# touch-24-v2.net
KiCad netlist of a schematic drawn in Altium Designer
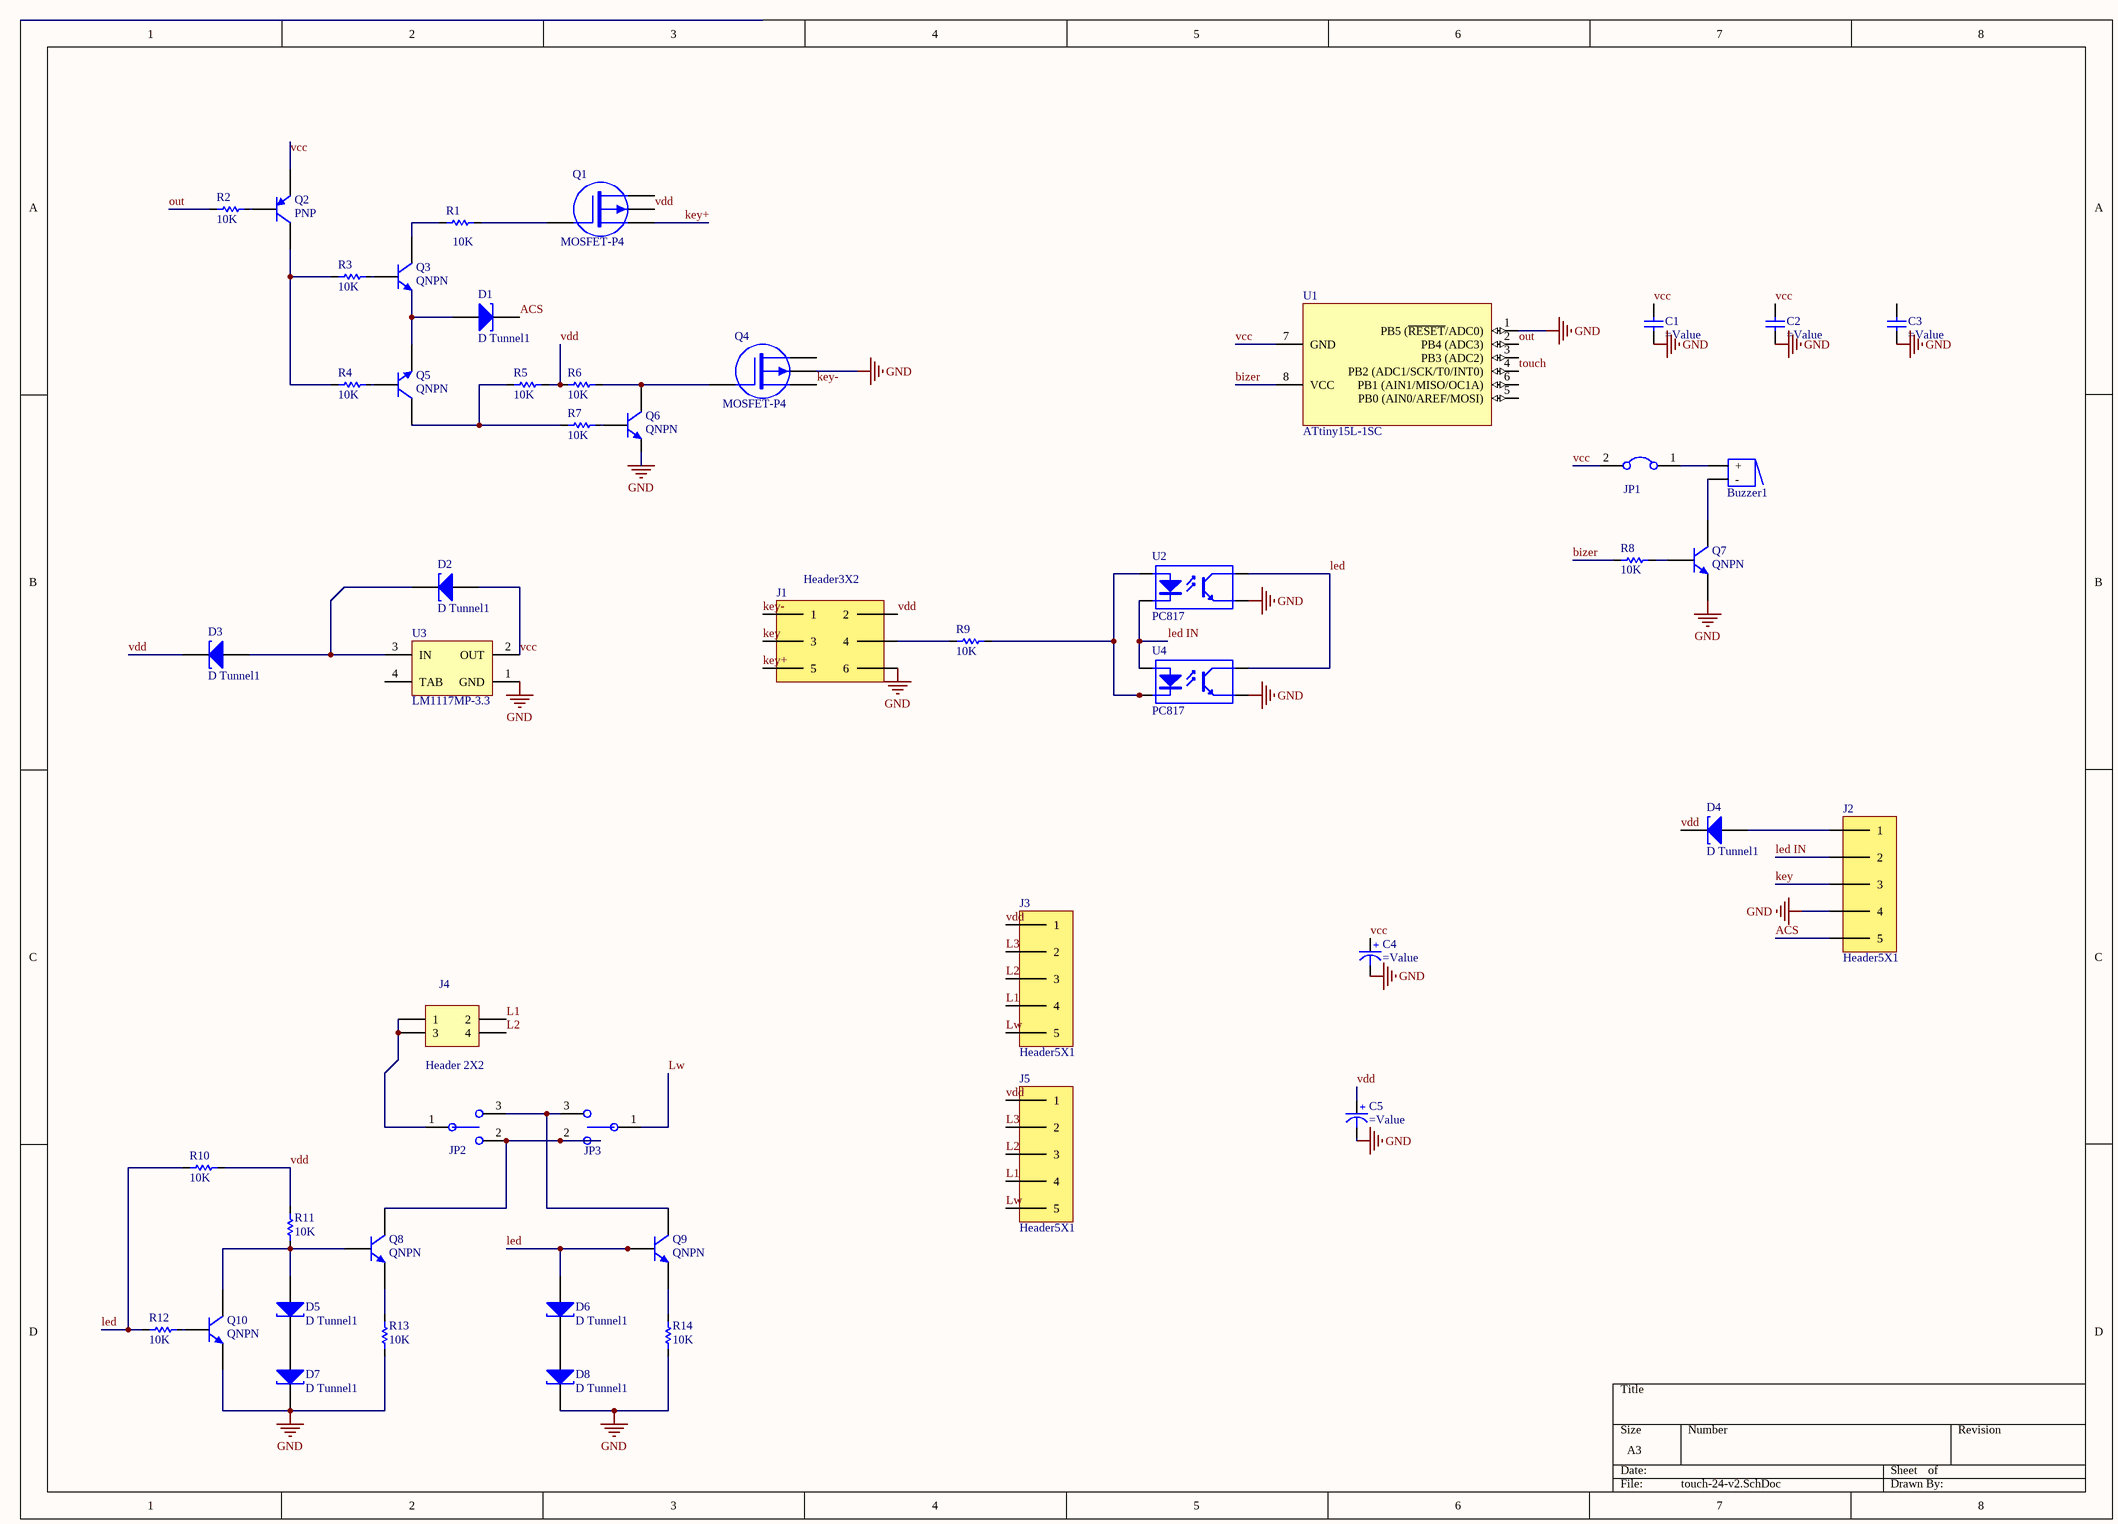
[diagram p0: touch-24-v2.SchDoc]

(export (version "E")
  (design (tool "Eeschema 10.0.6"))
  (components
    (comp (ref "Buzzer1")
      (value "Buzzer")
      (footprint "BUZZER")
      (fields (field (name "DESIGNER") "Seyed Mohsen Ghasemain"))
      (libsource (lib "PicPars.com_usefully_Library") (part "Buzzer"))
    )
    (comp (ref "C1")
      (value "~")
      (footprint "CAP 1206")
      (description "Capacitor")
      (libsource (lib "AltiumLib1") (part "Capacitor"))
    )
    (comp (ref "C2")
      (value "~")
      (footprint "CAP 1206")
      (description "Capacitor")
      (libsource (lib "AltiumLib1") (part "Capacitor"))
    )
    (comp (ref "C3")
      (value "~")
      (footprint "CAP 1206")
      (description "Capacitor")
      (libsource (lib "AltiumLib1") (part "Capacitor"))
    )
    (comp (ref "C4")
      (value "~")
      (footprint "ELEC-CAP-RAD10-20")
      (description "Electrolytic Capacitor")
      (libsource (lib "AltiumLib1") (part "Capacitor Electrolytic"))
    )
    (comp (ref "C5")
      (value "~")
      (footprint "ELEC-CAP-RAD15-30")
      (description "Electrolytic Capacitor")
      (libsource (lib "AltiumLib1") (part "Capacitor Electrolytic"))
    )
    (comp (ref "D1")
      (value "D Tunnel1")
      (footprint "3.2X1.6X1.1")
      (description "Tunnel Diode - RLC Model")
      (fields (field (name "PUBLISHER") "Altium Limited"))
      (libsource (lib "Miscellaneous Devices") (part "D Tunnel1"))
    )
    (comp (ref "D2")
      (value "D Tunnel1")
      (footprint "3.2X1.6X1.1")
      (description "Tunnel Diode - RLC Model")
      (fields (field (name "PUBLISHER") "Altium Limited"))
      (libsource (lib "Miscellaneous Devices") (part "D Tunnel1"))
    )
    (comp (ref "D3")
      (value "D Tunnel1")
      (footprint "3.2X1.6X1.1")
      (description "Tunnel Diode - RLC Model")
      (fields (field (name "PUBLISHER") "Altium Limited"))
      (libsource (lib "Miscellaneous Devices") (part "D Tunnel1"))
    )
    (comp (ref "D4")
      (value "D Tunnel1")
      (footprint "3.2X1.6X1.1")
      (description "Tunnel Diode - RLC Model")
      (fields (field (name "PUBLISHER") "Altium Limited"))
      (libsource (lib "Miscellaneous Devices") (part "D Tunnel1"))
    )
    (comp (ref "D5")
      (value "D Tunnel1")
      (footprint "3.2X1.6X1.1")
      (description "Tunnel Diode - RLC Model")
      (fields (field (name "PUBLISHER") "Altium Limited"))
      (libsource (lib "Miscellaneous Devices") (part "D Tunnel1"))
    )
    (comp (ref "D6")
      (value "D Tunnel1")
      (footprint "3.2X1.6X1.1")
      (description "Tunnel Diode - RLC Model")
      (fields (field (name "PUBLISHER") "Altium Limited"))
      (libsource (lib "Miscellaneous Devices") (part "D Tunnel1"))
    )
    (comp (ref "D7")
      (value "D Tunnel1")
      (footprint "3.2X1.6X1.1")
      (description "Tunnel Diode - RLC Model")
      (fields (field (name "PUBLISHER") "Altium Limited"))
      (libsource (lib "Miscellaneous Devices") (part "D Tunnel1"))
    )
    (comp (ref "D8")
      (value "D Tunnel1")
      (footprint "3.2X1.6X1.1")
      (description "Tunnel Diode - RLC Model")
      (fields (field (name "PUBLISHER") "Altium Limited"))
      (libsource (lib "Miscellaneous Devices") (part "D Tunnel1"))
    )
    (comp (ref "J1")
      (value "Header3X2")
      (footprint "HEADER 3X2")
      (libsource (lib "AltiumLib1") (part "Header3X2"))
    )
    (comp (ref "J2")
      (value "Header5X1")
      (footprint "HEADER 5X1")
      (libsource (lib "AltiumLib1") (part "Header5X1"))
    )
    (comp (ref "J3")
      (value "Header5X1")
      (footprint "HEADER 5X1")
      (libsource (lib "AltiumLib1") (part "Header5X1"))
    )
    (comp (ref "J4")
      (value "Header 2X2")
      (footprint "HDR2X2")
      (description "Header, 2-Pin, Dual row")
      (fields (field (name "PUBLISHER") "Altium Limited"))
      (libsource (lib "Miscellaneous Connectors") (part "Header 2X2"))
    )
    (comp (ref "J5")
      (value "Header5X1")
      (footprint "HEADER 5X1")
      (libsource (lib "AltiumLib1") (part "Header5X1"))
    )
    (comp (ref "JP1")
      (value "Jumper")
      (footprint "Header 2X1")
      (libsource (lib "AltiumLib1") (part "Jumper"))
    )
    (comp (ref "JP2")
      (value "Jumper Selector")
      (footprint "Jumper Selector")
      (libsource (lib "") (part "Jumper Selector_1"))
    )
    (comp (ref "JP3")
      (value "Jumper Selector")
      (footprint "Jumper Selector")
      (libsource (lib "AltiumLib1") (part "Jumper Selector"))
    )
    (comp (ref "Q1")
      (value "MOSFET-P4")
      (footprint "SOT223_N")
      (description "P-Channel MOSFET, Externally Terminated Substrate")
      (fields (field (name "PUBLISHER") "Altium Limited"))
      (libsource (lib "Miscellaneous Devices") (part "MOSFET-P4"))
    )
    (comp (ref "Q2")
      (value "PNP")
      (footprint "SOT-23B_N")
      (description "PNP Bipolar Transistor")
      (fields (field (name "PUBLISHER") "Altium Limited"))
      (libsource (lib "Miscellaneous Devices") (part "PNP"))
    )
    (comp (ref "Q3")
      (value "QNPN")
      (footprint "SOT-23B_L")
      (description "NPN Bipolar Transistor")
      (fields (field (name "PUBLISHER") "Altium Limited"))
      (libsource (lib "Miscellaneous Devices") (part "QNPN"))
    )
    (comp (ref "Q4")
      (value "MOSFET-P4")
      (footprint "SOT223_N")
      (description "P-Channel MOSFET, Externally Terminated Substrate")
      (fields (field (name "PUBLISHER") "Altium Limited"))
      (libsource (lib "Miscellaneous Devices") (part "MOSFET-P4"))
    )
    (comp (ref "Q5")
      (value "QNPN")
      (footprint "SOT-23B_L")
      (description "NPN Bipolar Transistor")
      (fields (field (name "PUBLISHER") "Altium Limited"))
      (libsource (lib "Miscellaneous Devices") (part "QNPN"))
    )
    (comp (ref "Q6")
      (value "QNPN")
      (footprint "SOT-23B_L")
      (description "NPN Bipolar Transistor")
      (fields (field (name "PUBLISHER") "Altium Limited"))
      (libsource (lib "Miscellaneous Devices") (part "QNPN"))
    )
    (comp (ref "Q7")
      (value "QNPN")
      (footprint "SOT-23B_L")
      (description "NPN Bipolar Transistor")
      (fields (field (name "PUBLISHER") "Altium Limited"))
      (libsource (lib "Miscellaneous Devices") (part "QNPN"))
    )
    (comp (ref "Q8")
      (value "QNPN")
      (footprint "SOT-23B_L")
      (description "NPN Bipolar Transistor")
      (fields (field (name "PUBLISHER") "Altium Limited"))
      (libsource (lib "Miscellaneous Devices") (part "QNPN"))
    )
    (comp (ref "Q9")
      (value "QNPN")
      (footprint "SOT-23B_L")
      (description "NPN Bipolar Transistor")
      (fields (field (name "PUBLISHER") "Altium Limited"))
      (libsource (lib "Miscellaneous Devices") (part "QNPN"))
    )
    (comp (ref "Q10")
      (value "QNPN")
      (footprint "SOT-23B_L")
      (description "NPN Bipolar Transistor")
      (fields (field (name "PUBLISHER") "Altium Limited"))
      (libsource (lib "Miscellaneous Devices") (part "QNPN"))
    )
    (comp (ref "R1")
      (value "10K")
      (footprint "RES 1206 (3216X08L)")
      (description "Resistor")
      (fields (field (name "TOLERANCE") "5%") (field (name "POWER") "1/4 W"))
      (libsource (lib "AltiumLib1") (part "Resistor"))
    )
    (comp (ref "R2")
      (value "10K")
      (footprint "RES 1206 (3216X08L)")
      (description "Resistor")
      (fields (field (name "TOLERANCE") "5%") (field (name "POWER") "1/4 W"))
      (libsource (lib "AltiumLib1") (part "Resistor"))
    )
    (comp (ref "R3")
      (value "10K")
      (footprint "RES 1206 (3216X08L)")
      (description "Resistor")
      (fields (field (name "TOLERANCE") "5%") (field (name "POWER") "1/4 W"))
      (libsource (lib "AltiumLib1") (part "Resistor"))
    )
    (comp (ref "R4")
      (value "10K")
      (footprint "RES 1206 (3216X08L)")
      (description "Resistor")
      (fields (field (name "TOLERANCE") "5%") (field (name "POWER") "1/4 W"))
      (libsource (lib "AltiumLib1") (part "Resistor"))
    )
    (comp (ref "R5")
      (value "10K")
      (footprint "RES 1206 (3216X08L)")
      (description "Resistor")
      (fields (field (name "TOLERANCE") "5%") (field (name "POWER") "1/4 W"))
      (libsource (lib "AltiumLib1") (part "Resistor"))
    )
    (comp (ref "R6")
      (value "10K")
      (footprint "RES 1206 (3216X08L)")
      (description "Resistor")
      (fields (field (name "TOLERANCE") "5%") (field (name "POWER") "1/4 W"))
      (libsource (lib "AltiumLib1") (part "Resistor"))
    )
    (comp (ref "R7")
      (value "10K")
      (footprint "RES 1206 (3216X08L)")
      (description "Resistor")
      (fields (field (name "TOLERANCE") "5%") (field (name "POWER") "1/4 W"))
      (libsource (lib "AltiumLib1") (part "Resistor"))
    )
    (comp (ref "R8")
      (value "10K")
      (footprint "RES 1206 (3216X08L)")
      (description "Resistor")
      (fields (field (name "TOLERANCE") "5%") (field (name "POWER") "1/4 W"))
      (libsource (lib "AltiumLib1") (part "Resistor"))
    )
    (comp (ref "R9")
      (value "10K")
      (footprint "RES 1206 (3216X08L)")
      (description "Resistor")
      (fields (field (name "TOLERANCE") "5%") (field (name "POWER") "1/4 W"))
      (libsource (lib "AltiumLib1") (part "Resistor"))
    )
    (comp (ref "R10")
      (value "10K")
      (footprint "RES 1206 (3216X08L)")
      (description "Resistor")
      (fields (field (name "TOLERANCE") "5%") (field (name "POWER") "1/4 W"))
      (libsource (lib "AltiumLib1") (part "Resistor"))
    )
    (comp (ref "R11")
      (value "10K")
      (footprint "RES 1206 (3216X08L)")
      (description "Resistor")
      (fields (field (name "TOLERANCE") "5%") (field (name "POWER") "1/4 W"))
      (libsource (lib "AltiumLib1") (part "Resistor"))
    )
    (comp (ref "R12")
      (value "10K")
      (footprint "RES 1206 (3216X08L)")
      (description "Resistor")
      (fields (field (name "TOLERANCE") "5%") (field (name "POWER") "1/4 W"))
      (libsource (lib "AltiumLib1") (part "Resistor"))
    )
    (comp (ref "R13")
      (value "10K")
      (footprint "RES 1206 (3216X08L)")
      (description "Resistor")
      (fields (field (name "TOLERANCE") "5%") (field (name "POWER") "1/4 W"))
      (libsource (lib "AltiumLib1") (part "Resistor"))
    )
    (comp (ref "R14")
      (value "10K")
      (footprint "RES 1206 (3216X08L)")
      (description "Resistor")
      (fields (field (name "TOLERANCE") "5%") (field (name "POWER") "1/4 W"))
      (libsource (lib "AltiumLib1") (part "Resistor"))
    )
    (comp (ref "U1")
      (value "ATtiny15L-1SC")
      (footprint "8S2_N")
      (description "8-Bit AVR Microcontroller with 1K Byte of Flash Memory")
      (fields (field (name "PUBLISHER") "Altium Limited"))
      (libsource (lib "Atmel Microcontroller 8-Bit AVR") (part "ATtiny15L-1SC"))
    )
    (comp (ref "U2")
      (value "PC817")
      (footprint "DIP4")
      (description "4-Pin Phototransistor Optocoupler")
      (libsource (lib "AltiumLib1") (part "OPTCOUPLER_01"))
    )
    (comp (ref "U3")
      (value "LM1117MP-3.3")
      (footprint "Miscellaneous Devices:SOT89L")
      (description "800mA Low-Dropout Linear Regulator")
      (fields
        (field (name "MANUFACTURER") "National Semiconductor")
        (field (name "DIGIKEYPARTNUMBER") "LM1117MP-3.3CT-ND")
        (field (name "PUBLISHER") "Altium Limited")
      )
      (libsource (lib "NSC LDO") (part "LM1117MP-3.3"))
    )
    (comp (ref "U4")
      (value "PC817")
      (footprint "DIP4")
      (description "4-Pin Phototransistor Optocoupler")
      (libsource (lib "AltiumLib1") (part "OPTCOUPLER_01"))
    )
  )
  (nets
    (net (code "1") (name "/ACS") (class "Default")
      (node (ref "D1") (pin "2") (pinfunction "K_2") (pintype "passive"))
      (node (ref "J2") (pin "5") (pinfunction "5_5") (pintype "passive"))
    )
    (net (code "2") (name "/L1") (class "Default")
      (node (ref "J3") (pin "4") (pinfunction "4_4") (pintype "passive"))
      (node (ref "J4") (pin "2") (pinfunction "2_2") (pintype "passive"))
      (node (ref "J5") (pin "4") (pinfunction "4_4") (pintype "passive"))
    )
    (net (code "3") (name "/L2") (class "Default")
      (node (ref "J3") (pin "3") (pinfunction "3_3") (pintype "passive"))
      (node (ref "J4") (pin "4") (pinfunction "4_4") (pintype "passive"))
      (node (ref "J5") (pin "3") (pinfunction "3_3") (pintype "passive"))
    )
    (net (code "4") (name "/L3") (class "Default")
      (node (ref "J3") (pin "2") (pinfunction "2_2") (pintype "passive"))
      (node (ref "J5") (pin "2") (pinfunction "2_2") (pintype "passive"))
    )
    (net (code "5") (name "/Lw") (class "Default")
      (node (ref "J3") (pin "5") (pinfunction "5_5") (pintype "passive"))
      (node (ref "J5") (pin "5") (pinfunction "5_5") (pintype "passive"))
      (node (ref "JP3") (pin "1") (pinfunction "1_1") (pintype "passive"))
    )
    (net (code "6") (name "/bizer") (class "Default")
      (node (ref "R8") (pin "1") (pinfunction "1_1") (pintype "passive"))
      (node (ref "U1") (pin "8") (pinfunction "VCC_8") (pintype "power_in"))
    )
    (net (code "7") (name "/key") (class "Default")
      (node (ref "J1") (pin "3") (pinfunction "3_3") (pintype "passive"))
      (node (ref "J2") (pin "3") (pinfunction "3_3") (pintype "passive"))
    )
    (net (code "8") (name "/key+") (class "Default")
      (node (ref "J1") (pin "5") (pinfunction "5_5") (pintype "passive"))
      (node (ref "Q1") (pin "4") (pinfunction "S_4") (pintype "passive"))
    )
    (net (code "9") (name "/key-") (class "Default")
      (node (ref "J1") (pin "1") (pinfunction "1_1") (pintype "passive"))
      (node (ref "Q4") (pin "4") (pinfunction "S_4") (pintype "passive"))
    )
    (net (code "10") (name "/led") (class "Default")
      (node (ref "D6") (pin "1") (pinfunction "A_1") (pintype "passive"))
      (node (ref "Q9") (pin "2") (pinfunction "B_2") (pintype "passive"))
      (node (ref "R10") (pin "1") (pinfunction "1_1") (pintype "passive"))
      (node (ref "R12") (pin "1") (pinfunction "1_1") (pintype "passive"))
      (node (ref "U2") (pin "4") (pinfunction "C_4") (pintype "passive"))
      (node (ref "U4") (pin "4") (pinfunction "C_4") (pintype "passive"))
    )
    (net (code "11") (name "/led IN") (class "Default")
      (node (ref "J2") (pin "2") (pinfunction "2_2") (pintype "passive"))
      (node (ref "U2") (pin "2") (pinfunction "K_2") (pintype "passive"))
      (node (ref "U4") (pin "1") (pinfunction "A_1") (pintype "passive"))
    )
    (net (code "12") (name "/out") (class "Default")
      (node (ref "R2") (pin "1") (pinfunction "1_1") (pintype "passive"))
      (node (ref "U1") (pin "2") (pinfunction "PB4_(ADC3)_2") (pintype "bidirectional"))
    )
    (net (code "13") (name "/touch") (class "Default")
      (node (ref "U1") (pin "4") (pinfunction "PB2_(ADC1/SCK/T0/INT0)_4") (pintype "bidirectional"))
    )
    (net (code "14") (name "/vcc") (class "Default")
      (node (ref "C1") (pin "2") (pinfunction "-_2") (pintype "passive"))
      (node (ref "C2") (pin "2") (pinfunction "-_2") (pintype "passive"))
      (node (ref "C4") (pin "2") (pinfunction "+_2") (pintype "passive"))
      (node (ref "D2") (pin "1") (pinfunction "A_1") (pintype "passive"))
      (node (ref "JP1") (pin "2") (pinfunction "2_2") (pintype "passive"))
      (node (ref "Q2") (pin "3") (pinfunction "E_3") (pintype "passive"))
      (node (ref "U1") (pin "7") (pinfunction "GND_7") (pintype "power_in"))
      (node (ref "U3") (pin "2") (pinfunction "OUT_2") (pintype "power_in"))
    )
    (net (code "15") (name "/vdd") (class "Default")
      (node (ref "C5") (pin "2") (pinfunction "+_2") (pintype "passive"))
      (node (ref "D3") (pin "2") (pinfunction "K_2") (pintype "passive"))
      (node (ref "D4") (pin "2") (pinfunction "K_2") (pintype "passive"))
      (node (ref "J1") (pin "2") (pinfunction "2_2") (pintype "passive"))
      (node (ref "J3") (pin "1") (pinfunction "1_1") (pintype "passive"))
      (node (ref "J5") (pin "1") (pinfunction "1_1") (pintype "passive"))
      (node (ref "Q1") (pin "3") (pinfunction "U_3") (pintype "passive"))
      (node (ref "R10") (pin "2") (pinfunction "2_2") (pintype "passive"))
      (node (ref "R11") (pin "2") (pinfunction "2_2") (pintype "passive"))
      (node (ref "R5") (pin "2") (pinfunction "2_2") (pintype "passive"))
      (node (ref "R6") (pin "1") (pinfunction "1_1") (pintype "passive"))
    )
    (net (code "16") (name "GND") (class "Default")
      (node (ref "C1") (pin "1") (pinfunction "+_1") (pintype "passive"))
      (node (ref "C2") (pin "1") (pinfunction "+_1") (pintype "passive"))
      (node (ref "C3") (pin "1") (pinfunction "+_1") (pintype "passive"))
      (node (ref "C4") (pin "1") (pinfunction "-_1") (pintype "passive"))
      (node (ref "C5") (pin "1") (pinfunction "-_1") (pintype "passive"))
      (node (ref "D7") (pin "2") (pinfunction "K_2") (pintype "passive"))
      (node (ref "D8") (pin "2") (pinfunction "K_2") (pintype "passive"))
      (node (ref "J1") (pin "6") (pinfunction "6_6") (pintype "passive"))
      (node (ref "J2") (pin "4") (pinfunction "4_4") (pintype "passive"))
      (node (ref "Q10") (pin "3") (pinfunction "E_3") (pintype "passive"))
      (node (ref "Q4") (pin "3") (pinfunction "U_3") (pintype "passive"))
      (node (ref "Q6") (pin "3") (pinfunction "E_3") (pintype "passive"))
      (node (ref "Q7") (pin "3") (pinfunction "E_3") (pintype "passive"))
      (node (ref "R13") (pin "1") (pinfunction "1_1") (pintype "passive"))
      (node (ref "R14") (pin "1") (pinfunction "1_1") (pintype "passive"))
      (node (ref "U1") (pin "1") (pinfunction "PB5_(~{RESET}/ADC0)_1") (pintype "bidirectional"))
      (node (ref "U2") (pin "3") (pinfunction "E_3") (pintype "passive"))
      (node (ref "U3") (pin "1") (pinfunction "GND_1") (pintype "power_in"))
      (node (ref "U4") (pin "3") (pinfunction "E_3") (pintype "passive"))
    )
    (net (code "17") (name "Net-(Buzzer1-+)") (class "Default")
      (node (ref "Buzzer1") (pin "1") (pinfunction "+_1") (pintype "passive"))
      (node (ref "JP1") (pin "1") (pinfunction "1_1") (pintype "passive"))
    )
    (net (code "18") (name "Net-(Buzzer1--)") (class "Default")
      (node (ref "Buzzer1") (pin "2") (pinfunction "-_2") (pintype "passive"))
      (node (ref "Q7") (pin "1") (pinfunction "C_1") (pintype "passive"))
    )
    (net (code "19") (name "Net-(D1-A)") (class "Default")
      (node (ref "D1") (pin "1") (pinfunction "A_1") (pintype "passive"))
      (node (ref "Q3") (pin "3") (pinfunction "E_3") (pintype "passive"))
      (node (ref "Q5") (pin "3") (pinfunction "E_3") (pintype "passive"))
    )
    (net (code "20") (name "Net-(D2-K)") (class "Default")
      (node (ref "D2") (pin "2") (pinfunction "K_2") (pintype "passive"))
      (node (ref "D3") (pin "1") (pinfunction "A_1") (pintype "passive"))
      (node (ref "U3") (pin "3") (pinfunction "IN_3") (pintype "power_in"))
    )
    (net (code "21") (name "Net-(D4-A)") (class "Default")
      (node (ref "D4") (pin "1") (pinfunction "A_1") (pintype "passive"))
      (node (ref "J2") (pin "1") (pinfunction "1_1") (pintype "passive"))
    )
    (net (code "22") (name "Net-(D5-A)") (class "Default")
      (node (ref "D5") (pin "1") (pinfunction "A_1") (pintype "passive"))
      (node (ref "Q10") (pin "1") (pinfunction "C_1") (pintype "passive"))
      (node (ref "Q8") (pin "2") (pinfunction "B_2") (pintype "passive"))
      (node (ref "R11") (pin "1") (pinfunction "1_1") (pintype "passive"))
    )
    (net (code "23") (name "Net-(D5-K)") (class "Default")
      (node (ref "D5") (pin "2") (pinfunction "K_2") (pintype "passive"))
      (node (ref "D7") (pin "1") (pinfunction "A_1") (pintype "passive"))
    )
    (net (code "24") (name "Net-(D6-K)") (class "Default")
      (node (ref "D6") (pin "2") (pinfunction "K_2") (pintype "passive"))
      (node (ref "D8") (pin "1") (pinfunction "A_1") (pintype "passive"))
    )
    (net (code "25") (name "Net-(J1-Pad4)") (class "Default")
      (node (ref "J1") (pin "4") (pinfunction "4_4") (pintype "passive"))
      (node (ref "R9") (pin "1") (pinfunction "1_1") (pintype "passive"))
    )
    (net (code "26") (name "Net-(J4-Pad1)") (class "Default")
      (node (ref "J4") (pin "1") (pinfunction "1_1") (pintype "passive"))
      (node (ref "J4") (pin "3") (pinfunction "3_3") (pintype "passive"))
      (node (ref "JP2") (pin "1") (pinfunction "1_1") (pintype "passive"))
    )
    (net (code "27") (name "Net-(Q1-G)") (class "Default")
      (node (ref "Q1") (pin "1") (pinfunction "G_1") (pintype "passive"))
      (node (ref "R1") (pin "2") (pinfunction "2_2") (pintype "passive"))
    )
    (net (code "28") (name "Net-(Q2-B)") (class "Default")
      (node (ref "Q2") (pin "2") (pinfunction "B_2") (pintype "passive"))
      (node (ref "R2") (pin "2") (pinfunction "2_2") (pintype "passive"))
    )
    (net (code "29") (name "Net-(Q2-C)") (class "Default")
      (node (ref "Q2") (pin "1") (pinfunction "C_1") (pintype "passive"))
      (node (ref "R3") (pin "1") (pinfunction "1_1") (pintype "passive"))
      (node (ref "R4") (pin "1") (pinfunction "1_1") (pintype "passive"))
    )
    (net (code "30") (name "Net-(Q3-B)") (class "Default")
      (node (ref "Q3") (pin "2") (pinfunction "B_2") (pintype "passive"))
      (node (ref "R3") (pin "2") (pinfunction "2_2") (pintype "passive"))
    )
    (net (code "31") (name "Net-(Q3-C)") (class "Default")
      (node (ref "Q3") (pin "1") (pinfunction "C_1") (pintype "passive"))
      (node (ref "R1") (pin "1") (pinfunction "1_1") (pintype "passive"))
    )
    (net (code "32") (name "Net-(Q4-G)") (class "Default")
      (node (ref "Q4") (pin "1") (pinfunction "G_1") (pintype "passive"))
      (node (ref "Q6") (pin "1") (pinfunction "C_1") (pintype "passive"))
      (node (ref "R6") (pin "2") (pinfunction "2_2") (pintype "passive"))
    )
    (net (code "33") (name "Net-(Q5-B)") (class "Default")
      (node (ref "Q5") (pin "2") (pinfunction "B_2") (pintype "passive"))
      (node (ref "R4") (pin "2") (pinfunction "2_2") (pintype "passive"))
    )
    (net (code "34") (name "Net-(Q5-C)") (class "Default")
      (node (ref "Q5") (pin "1") (pinfunction "C_1") (pintype "passive"))
      (node (ref "R5") (pin "1") (pinfunction "1_1") (pintype "passive"))
      (node (ref "R7") (pin "1") (pinfunction "1_1") (pintype "passive"))
    )
    (net (code "35") (name "Net-(Q6-B)") (class "Default")
      (node (ref "Q6") (pin "2") (pinfunction "B_2") (pintype "passive"))
      (node (ref "R7") (pin "2") (pinfunction "2_2") (pintype "passive"))
    )
    (net (code "36") (name "Net-(Q7-B)") (class "Default")
      (node (ref "Q7") (pin "2") (pinfunction "B_2") (pintype "passive"))
      (node (ref "R8") (pin "2") (pinfunction "2_2") (pintype "passive"))
    )
    (net (code "37") (name "Net-(Q8-C)") (class "Default")
      (node (ref "JP2") (pin "2") (pinfunction "2_2") (pintype "passive"))
      (node (ref "JP3") (pin "2") (pinfunction "2_2") (pintype "passive"))
      (node (ref "Q8") (pin "1") (pinfunction "C_1") (pintype "passive"))
    )
    (net (code "38") (name "Net-(Q8-E)") (class "Default")
      (node (ref "Q8") (pin "3") (pinfunction "E_3") (pintype "passive"))
      (node (ref "R13") (pin "2") (pinfunction "2_2") (pintype "passive"))
    )
    (net (code "39") (name "Net-(Q9-C)") (class "Default")
      (node (ref "JP2") (pin "3") (pinfunction "3_3") (pintype "passive"))
      (node (ref "JP3") (pin "3") (pinfunction "3_3") (pintype "passive"))
      (node (ref "Q9") (pin "1") (pinfunction "C_1") (pintype "passive"))
    )
    (net (code "40") (name "Net-(Q9-E)") (class "Default")
      (node (ref "Q9") (pin "3") (pinfunction "E_3") (pintype "passive"))
      (node (ref "R14") (pin "2") (pinfunction "2_2") (pintype "passive"))
    )
    (net (code "41") (name "Net-(Q10-B)") (class "Default")
      (node (ref "Q10") (pin "2") (pinfunction "B_2") (pintype "passive"))
      (node (ref "R12") (pin "2") (pinfunction "2_2") (pintype "passive"))
    )
    (net (code "42") (name "Net-(U2-A)") (class "Default")
      (node (ref "R9") (pin "2") (pinfunction "2_2") (pintype "passive"))
      (node (ref "U2") (pin "1") (pinfunction "A_1") (pintype "passive"))
      (node (ref "U4") (pin "2") (pinfunction "K_2") (pintype "passive"))
    )
    (net (code "43") (name "unconnected-(C3---Pad2)") (class "Default")
      (node (ref "C3") (pin "2") (pinfunction "-_2") (pintype "passive"))
    )
    (net (code "44") (name "unconnected-(Q1-D-Pad2)") (class "Default")
      (node (ref "Q1") (pin "2") (pinfunction "D_2") (pintype "passive"))
    )
    (net (code "45") (name "unconnected-(Q4-D-Pad2)") (class "Default")
      (node (ref "Q4") (pin "2") (pinfunction "D_2") (pintype "passive"))
    )
    (net (code "46") (name "unconnected-(U1-PB0_(AIN0{slash}AREF{slash}MOSI)-Pad5)") (class "Default")
      (node (ref "U1") (pin "5") (pinfunction "PB0_(AIN0/AREF/MOSI)_5") (pintype "bidirectional"))
    )
    (net (code "47") (name "unconnected-(U1-PB1_(AIN1{slash}MISO{slash}OC1A)-Pad6)") (class "Default")
      (node (ref "U1") (pin "6") (pinfunction "PB1_(AIN1/MISO/OC1A)_6") (pintype "bidirectional"))
    )
    (net (code "48") (name "unconnected-(U1-PB3_(ADC2)-Pad3)") (class "Default")
      (node (ref "U1") (pin "3") (pinfunction "PB3_(ADC2)_3") (pintype "bidirectional"))
    )
    (net (code "49") (name "unconnected-(U3-TAB-Pad4)") (class "Default")
      (node (ref "U3") (pin "4") (pinfunction "TAB_4") (pintype "power_in"))
    )
  )
)
